# TCS3200_board.net
KiCad netlist of a schematic drawn in EAGLE
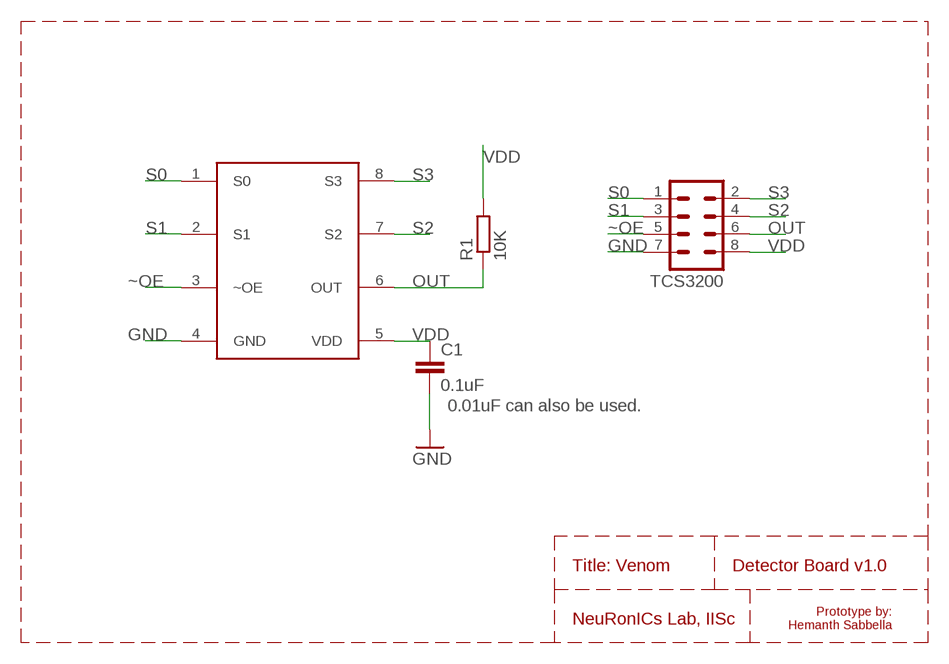
[diagram p0: schematic, sheet 1]

(export (version "E")
  (design (tool "Eeschema 10.0.6"))
  (components
    (comp (ref "C1")
      (value "0.1uF")
      (footprint "eagle-import:C0805")
      (libsource (lib "eagle-import") (part "C-EUC0805"))
    )
    (comp (ref "R1")
      (value "10K")
      (footprint "eagle-import:R0805")
      (libsource (lib "eagle-import") (part "R-EU_R0805"))
    )
    (comp (ref "TCS3200")
      (value "MA04-2")
      (footprint "eagle-import:MA04-2")
      (libsource (lib "eagle-import") (part "MA04-2"))
    )
    (comp (ref "U$1")
      (value "TCS3200")
      (footprint "eagle-import:TCS3200")
      (libsource (lib "eagle-import") (part "TCS3200"))
    )
  )
  (nets
    (net (code "1") (name "/OUT") (class "Default")
      (node (ref "R1") (pin "1") (pinfunction "1_1") (pintype "passive"))
      (node (ref "TCS3200") (pin "6") (pinfunction "6_6") (pintype "passive"))
      (node (ref "U$1") (pin "6") (pinfunction "OUT_6") (pintype "bidirectional"))
    )
    (net (code "2") (name "/S0") (class "Default")
      (node (ref "TCS3200") (pin "1") (pinfunction "1_1") (pintype "passive"))
      (node (ref "U$1") (pin "1") (pinfunction "S0_1") (pintype "bidirectional"))
    )
    (net (code "3") (name "/S1") (class "Default")
      (node (ref "TCS3200") (pin "3") (pinfunction "3_3") (pintype "passive"))
      (node (ref "U$1") (pin "2") (pinfunction "S1_2") (pintype "bidirectional"))
    )
    (net (code "4") (name "/S2") (class "Default")
      (node (ref "TCS3200") (pin "4") (pinfunction "4_4") (pintype "passive"))
      (node (ref "U$1") (pin "7") (pinfunction "S2_7") (pintype "bidirectional"))
    )
    (net (code "5") (name "/S3") (class "Default")
      (node (ref "TCS3200") (pin "2") (pinfunction "2_2") (pintype "passive"))
      (node (ref "U$1") (pin "8") (pinfunction "S3_8") (pintype "bidirectional"))
    )
    (net (code "6") (name "/VDD") (class "Default")
      (node (ref "C1") (pin "1") (pinfunction "1_1") (pintype "passive"))
      (node (ref "R1") (pin "2") (pinfunction "2_2") (pintype "passive"))
      (node (ref "TCS3200") (pin "8") (pinfunction "8_8") (pintype "passive"))
      (node (ref "U$1") (pin "5") (pinfunction "VDD_5") (pintype "bidirectional"))
    )
    (net (code "7") (name "/~{OE}") (class "Default")
      (node (ref "TCS3200") (pin "5") (pinfunction "5_5") (pintype "passive"))
      (node (ref "U$1") (pin "3") (pinfunction "~{OE}_3") (pintype "bidirectional"))
    )
    (net (code "8") (name "GND") (class "Default")
      (node (ref "C1") (pin "2") (pinfunction "2_2") (pintype "passive"))
      (node (ref "TCS3200") (pin "7") (pinfunction "7_7") (pintype "passive"))
      (node (ref "U$1") (pin "4") (pinfunction "GND_4") (pintype "bidirectional"))
    )
  )
)
